# iigs.net
KiCad netlist of a schematic drawn in EAGLE
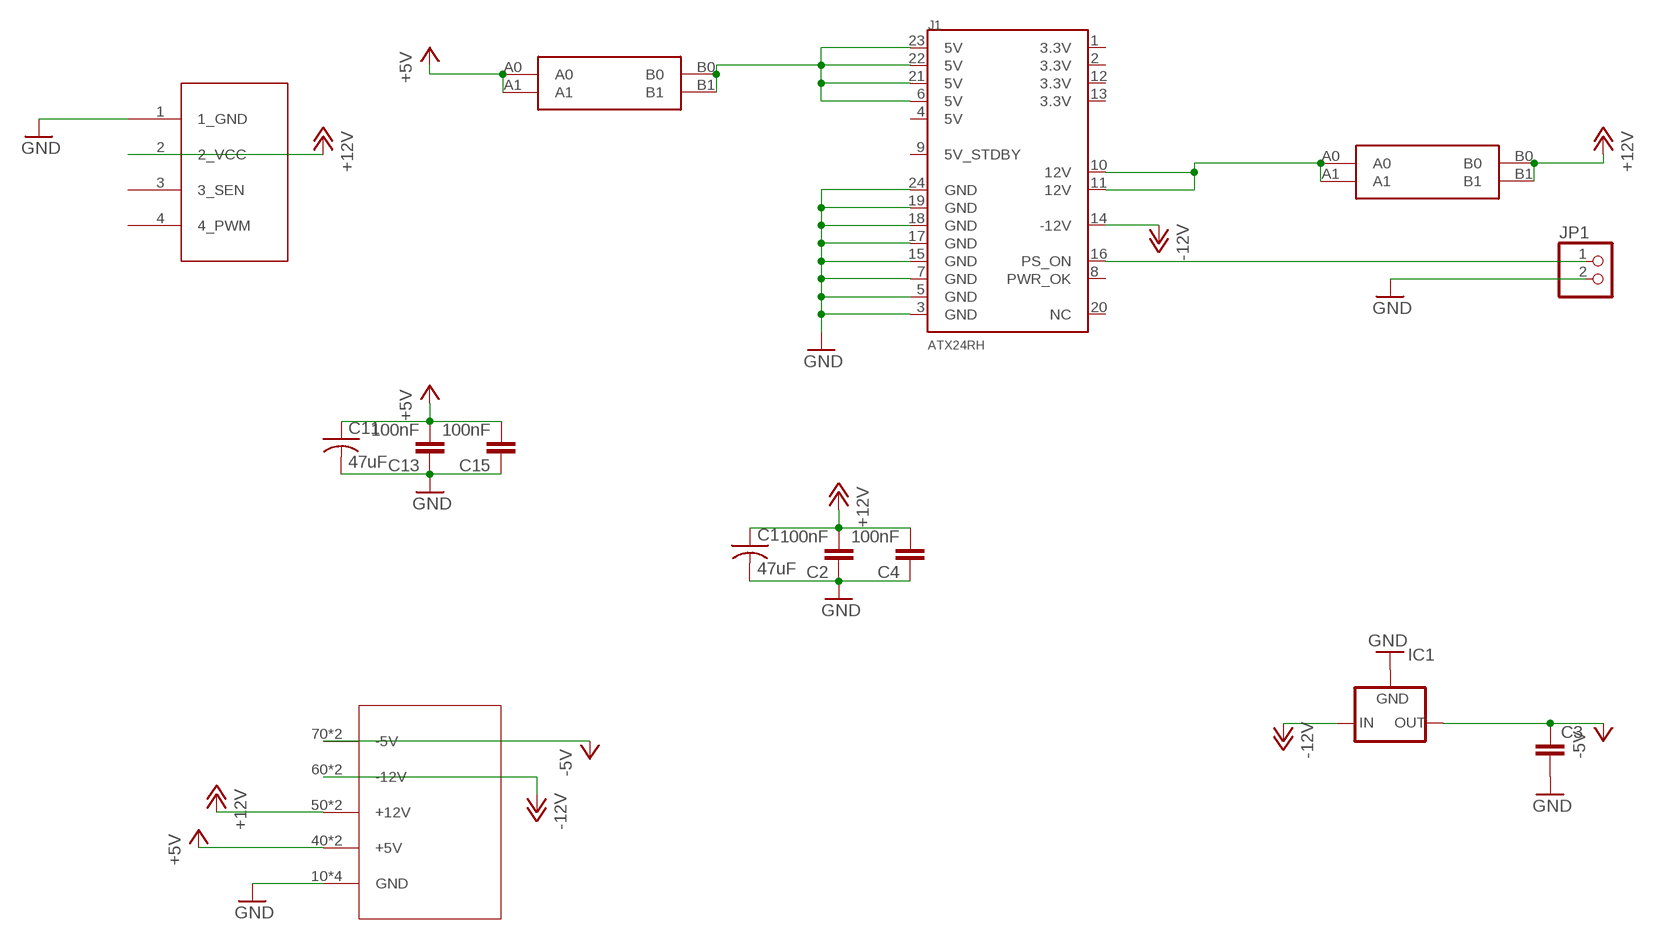
[diagram p0: schematic, sheet 1]

(export (version "E")
  (design (tool "Eeschema 10.0.6"))
  (components
    (comp (ref "C1")
      (value "47uF")
      (footprint "eagle-import:C1210")
      (libsource (lib "eagle-import") (part "C-USC1210"))
    )
    (comp (ref "C2")
      (value "100nF")
      (footprint "eagle-import:0805@1")
      (libsource (lib "eagle-import") (part "CAP0805"))
    )
    (comp (ref "C3")
      (value "C5/2.5")
      (footprint "eagle-import:C5B2.5")
      (libsource (lib "eagle-import") (part "C5/2.5"))
    )
    (comp (ref "C4")
      (value "100nF")
      (footprint "eagle-import:0805@1")
      (libsource (lib "eagle-import") (part "CAP0805"))
    )
    (comp (ref "C11")
      (value "47uF")
      (footprint "eagle-import:C1210")
      (libsource (lib "eagle-import") (part "C-USC1210"))
    )
    (comp (ref "C13")
      (value "100nF")
      (footprint "eagle-import:0805@1")
      (libsource (lib "eagle-import") (part "CAP0805"))
    )
    (comp (ref "C15")
      (value "100nF")
      (footprint "eagle-import:0805@1")
      (libsource (lib "eagle-import") (part "CAP0805"))
    )
    (comp (ref "IC1")
      (value "79XXS")
      (footprint "eagle-import:79XXS")
      (libsource (lib "eagle-import") (part "79XXS"))
    )
    (comp (ref "J1")
      (value "ATX24RH")
      (footprint "eagle-import:ATX24_RIGHT_ANGLE")
      (libsource (lib "eagle-import") (part "ATX24RH"))
    )
    (comp (ref "JP1")
      (value "PINHD-1X2")
      (footprint "eagle-import:1X02")
      (libsource (lib "eagle-import") (part "PINHD-1X2"))
    )
    (comp (ref "JP4")
      (value "4PIN_FAN")
      (footprint "eagle-import:1X04")
      (libsource (lib "eagle-import") (part "4PIN_FAN"))
    )
    (comp (ref "U$1")
      (value "CAR_FUSE_HOLDER3IN1")
      (footprint "eagle-import:FUSE_HOLDER_3IN1")
      (libsource (lib "eagle-import") (part "CAR_FUSE_HOLDER3IN1"))
    )
    (comp (ref "U$2")
      (value "CAR_FUSE_HOLDER3IN1")
      (footprint "eagle-import:FUSE_HOLDER_3IN1")
      (libsource (lib "eagle-import") (part "CAR_FUSE_HOLDER3IN1"))
    )
    (comp (ref "U$7")
      (value "3.96_FEM_IIGS")
      (footprint "eagle-import:3.96_FEMALE_IIGS_GAP")
      (libsource (lib "eagle-import") (part "3.96_FEM_IIGS"))
    )
  )
  (nets
    (net (code "1") (name "+5V") (class "Default")
      (node (ref "C11") (pin "1") (pinfunction "1_1") (pintype "passive"))
      (node (ref "C13") (pin "2") (pinfunction "2_2") (pintype "passive"))
      (node (ref "C15") (pin "2") (pinfunction "2_2") (pintype "passive"))
      (node (ref "U$1") (pin "A0") (pinfunction "A0_A0") (pintype "bidirectional"))
      (node (ref "U$1") (pin "A1") (pinfunction "A1_A1") (pintype "bidirectional"))
      (node (ref "U$7") (pin "40") (pinfunction "+5V_40") (pintype "bidirectional"))
      (node (ref "U$7") (pin "41") (pinfunction "+5V_41") (pintype "bidirectional"))
    )
    (net (code "2") (name "+12V") (class "Default")
      (node (ref "C1") (pin "1") (pinfunction "1_1") (pintype "passive"))
      (node (ref "C2") (pin "2") (pinfunction "2_2") (pintype "passive"))
      (node (ref "C4") (pin "2") (pinfunction "2_2") (pintype "passive"))
      (node (ref "JP4") (pin "2") (pinfunction "2_VCC_2") (pintype "passive"))
      (node (ref "U$2") (pin "B0") (pinfunction "B0_B0") (pintype "bidirectional"))
      (node (ref "U$2") (pin "B1") (pinfunction "B1_B1") (pintype "bidirectional"))
      (node (ref "U$7") (pin "50") (pinfunction "+12V_50") (pintype "bidirectional"))
      (node (ref "U$7") (pin "51") (pinfunction "+12V_51") (pintype "bidirectional"))
    )
    (net (code "3") (name "-5V") (class "Default")
      (node (ref "C3") (pin "1") (pinfunction "1_1") (pintype "passive"))
      (node (ref "IC1") (pin "OUT") (pinfunction "OUT_OUT") (pintype "passive"))
      (node (ref "U$7") (pin "70") (pinfunction "-5V_70") (pintype "bidirectional"))
      (node (ref "U$7") (pin "71") (pinfunction "-5V_71") (pintype "bidirectional"))
    )
    (net (code "4") (name "-12V") (class "Default")
      (node (ref "IC1") (pin "IN") (pinfunction "IN_IN") (pintype "input"))
      (node (ref "J1") (pin "14") (pinfunction "-12V_14") (pintype "bidirectional"))
      (node (ref "U$7") (pin "60") (pinfunction "-12V_60") (pintype "bidirectional"))
      (node (ref "U$7") (pin "61") (pinfunction "-12V_61") (pintype "bidirectional"))
    )
    (net (code "5") (name "GND") (class "Default")
      (node (ref "C1") (pin "2") (pinfunction "2_2") (pintype "passive"))
      (node (ref "C11") (pin "2") (pinfunction "2_2") (pintype "passive"))
      (node (ref "C13") (pin "1") (pinfunction "1_1") (pintype "passive"))
      (node (ref "C15") (pin "1") (pinfunction "1_1") (pintype "passive"))
      (node (ref "C2") (pin "1") (pinfunction "1_1") (pintype "passive"))
      (node (ref "C3") (pin "2") (pinfunction "2_2") (pintype "passive"))
      (node (ref "C4") (pin "1") (pinfunction "1_1") (pintype "passive"))
      (node (ref "IC1") (pin "GND") (pinfunction "GND_GND") (pintype "input"))
      (node (ref "J1") (pin "15") (pinfunction "GND_15") (pintype "bidirectional"))
      (node (ref "J1") (pin "17") (pinfunction "GND_17") (pintype "bidirectional"))
      (node (ref "J1") (pin "18") (pinfunction "GND_18") (pintype "bidirectional"))
      (node (ref "J1") (pin "19") (pinfunction "GND_19") (pintype "bidirectional"))
      (node (ref "J1") (pin "24") (pinfunction "GND_24") (pintype "bidirectional"))
      (node (ref "J1") (pin "3") (pinfunction "GND_3") (pintype "bidirectional"))
      (node (ref "J1") (pin "5") (pinfunction "GND_5") (pintype "bidirectional"))
      (node (ref "J1") (pin "7") (pinfunction "GND_7") (pintype "bidirectional"))
      (node (ref "JP1") (pin "2") (pinfunction "2_2") (pintype "passive"))
      (node (ref "JP4") (pin "1") (pinfunction "1_GND_1") (pintype "passive"))
      (node (ref "U$7") (pin "10") (pinfunction "GND_10") (pintype "bidirectional"))
      (node (ref "U$7") (pin "11") (pinfunction "GND_11") (pintype "bidirectional"))
      (node (ref "U$7") (pin "20") (pinfunction "GND_20") (pintype "bidirectional"))
      (node (ref "U$7") (pin "21") (pinfunction "GND_21") (pintype "bidirectional"))
    )
    (net (code "6") (name "Net-(J1-5V-Pad21)") (class "Default")
      (node (ref "J1") (pin "21") (pinfunction "5V_21") (pintype "bidirectional"))
      (node (ref "J1") (pin "22") (pinfunction "5V_22") (pintype "bidirectional"))
      (node (ref "J1") (pin "23") (pinfunction "5V_23") (pintype "bidirectional"))
      (node (ref "J1") (pin "6") (pinfunction "5V_6") (pintype "bidirectional"))
      (node (ref "U$1") (pin "B0") (pinfunction "B0_B0") (pintype "bidirectional"))
      (node (ref "U$1") (pin "B1") (pinfunction "B1_B1") (pintype "bidirectional"))
    )
    (net (code "7") (name "Net-(J1-12V-Pad10)") (class "Default")
      (node (ref "J1") (pin "10") (pinfunction "12V_10") (pintype "bidirectional"))
      (node (ref "J1") (pin "11") (pinfunction "12V_11") (pintype "bidirectional"))
      (node (ref "U$2") (pin "A0") (pinfunction "A0_A0") (pintype "bidirectional"))
      (node (ref "U$2") (pin "A1") (pinfunction "A1_A1") (pintype "bidirectional"))
    )
    (net (code "8") (name "Net-(J1-PS_ON)") (class "Default")
      (node (ref "J1") (pin "16") (pinfunction "PS_ON_16") (pintype "bidirectional"))
      (node (ref "JP1") (pin "1") (pinfunction "1_1") (pintype "passive"))
    )
    (net (code "9") (name "unconnected-(J1-3.3V-Pad1)") (class "Default")
      (node (ref "J1") (pin "1") (pinfunction "3.3V_1") (pintype "bidirectional"))
    )
    (net (code "10") (name "unconnected-(J1-3.3V-Pad2)") (class "Default")
      (node (ref "J1") (pin "2") (pinfunction "3.3V_2") (pintype "bidirectional"))
    )
    (net (code "11") (name "unconnected-(J1-3.3V-Pad12)") (class "Default")
      (node (ref "J1") (pin "12") (pinfunction "3.3V_12") (pintype "bidirectional"))
    )
    (net (code "12") (name "unconnected-(J1-3.3V-Pad13)") (class "Default")
      (node (ref "J1") (pin "13") (pinfunction "3.3V_13") (pintype "bidirectional"))
    )
    (net (code "13") (name "unconnected-(J1-5V-Pad4)") (class "Default")
      (node (ref "J1") (pin "4") (pinfunction "5V_4") (pintype "bidirectional"))
    )
    (net (code "14") (name "unconnected-(J1-5V_STDBY-Pad9)") (class "Default")
      (node (ref "J1") (pin "9") (pinfunction "5V_STDBY_9") (pintype "bidirectional"))
    )
    (net (code "15") (name "unconnected-(J1-NC-Pad20)") (class "Default")
      (node (ref "J1") (pin "20") (pinfunction "NC_20") (pintype "bidirectional"))
    )
    (net (code "16") (name "unconnected-(J1-PWR_OK-Pad8)") (class "Default")
      (node (ref "J1") (pin "8") (pinfunction "PWR_OK_8") (pintype "bidirectional"))
    )
    (net (code "17") (name "unconnected-(JP4-3_SEN-Pad3)") (class "Default")
      (node (ref "JP4") (pin "3") (pinfunction "3_SEN_3") (pintype "passive"))
    )
    (net (code "18") (name "unconnected-(JP4-4_PWM-Pad4)") (class "Default")
      (node (ref "JP4") (pin "4") (pinfunction "4_PWM_4") (pintype "passive"))
    )
  )
)
